# qtip_rev2.net
KiCad netlist of a schematic drawn in EAGLE
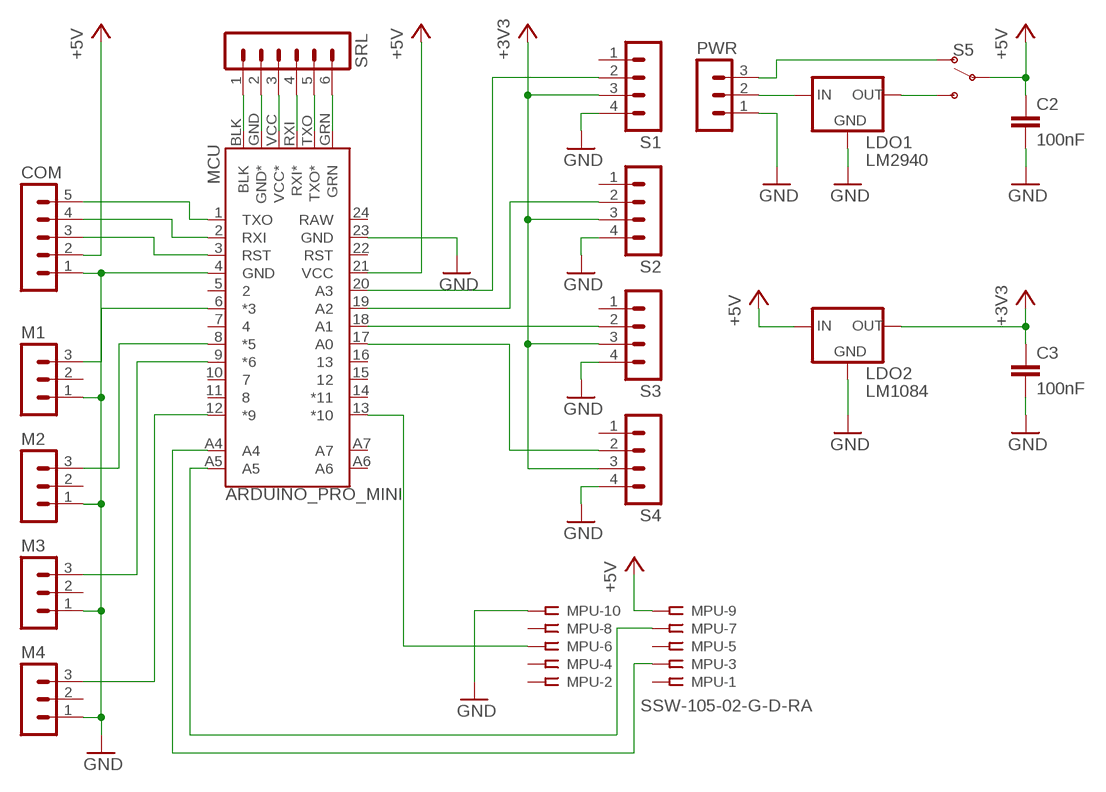
[diagram p0: schematic, sheet 1]

(export (version "E")
  (design (tool "Eeschema 10.0.6"))
  (components
    (comp (ref "C2")
      (value "100nF")
      (footprint "eagle-import:C025-024X044")
      (libsource (lib "eagle-import") (part "C-EU025-024X044"))
    )
    (comp (ref "C3")
      (value "100nF")
      (footprint "eagle-import:C025-024X044")
      (libsource (lib "eagle-import") (part "C-EU025-024X044"))
    )
    (comp (ref "COM")
      (value "MA05-1")
      (footprint "eagle-import:MA05-1")
      (fields (field (name "SPICEPREFIX") "X"))
      (libsource (lib "eagle-import") (part "MA05-1"))
    )
    (comp (ref "LDO1")
      (value "LM2940")
      (footprint "eagle-import:78XXL")
      (libsource (lib "eagle-import") (part "V_REG_LD1117VXX"))
    )
    (comp (ref "LDO2")
      (value "LM1084")
      (footprint "eagle-import:78XXL")
      (libsource (lib "eagle-import") (part "V_REG_LD1117VXX"))
    )
    (comp (ref "M1")
      (value "MA03-1")
      (footprint "eagle-import:MA03-1")
      (libsource (lib "eagle-import") (part "MA03-1"))
    )
    (comp (ref "M2")
      (value "MA03-1")
      (footprint "eagle-import:MA03-1")
      (libsource (lib "eagle-import") (part "MA03-1"))
    )
    (comp (ref "M3")
      (value "MA03-1")
      (footprint "eagle-import:MA03-1")
      (libsource (lib "eagle-import") (part "MA03-1"))
    )
    (comp (ref "M4")
      (value "MA03-1")
      (footprint "eagle-import:MA03-1")
      (libsource (lib "eagle-import") (part "MA03-1"))
    )
    (comp (ref "MCU")
      (value "ARDUINO_PRO_MINI")
      (footprint "eagle-import:ARDUINO_PRO_MINI")
      (libsource (lib "eagle-import") (part "ARDUINO_PRO_MINI"))
    )
    (comp (ref "MPU")
      (value "SSW-105-02-G-D-RA")
      (footprint "eagle-import:SSW-105-02-G-D-RA")
      (fields (field (name "MF") "Samtec Inc."))
      (libsource (lib "eagle-import") (part "SSW-105-02-G-D-RA"))
    )
    (comp (ref "PWR")
      (value "MA03-1")
      (footprint "eagle-import:MA03-1")
      (libsource (lib "eagle-import") (part "MA03-1"))
    )
    (comp (ref "S1")
      (value "MA04-1")
      (footprint "eagle-import:MA04-1")
      (libsource (lib "eagle-import") (part "MA04-1"))
    )
    (comp (ref "S2")
      (value "MA04-1")
      (footprint "eagle-import:MA04-1")
      (libsource (lib "eagle-import") (part "MA04-1"))
    )
    (comp (ref "S3")
      (value "MA04-1")
      (footprint "eagle-import:MA04-1")
      (libsource (lib "eagle-import") (part "MA04-1"))
    )
    (comp (ref "S4")
      (value "MA04-1")
      (footprint "eagle-import:MA04-1")
      (libsource (lib "eagle-import") (part "MA04-1"))
    )
    (comp (ref "S5")
      (value "SWITCH-SPDT-PTH-11.6X4.0MM")
      (footprint "eagle-import:SWITCH_SPDT_PTH_11.6X4.0MM")
      (libsource (lib "eagle-import") (part "SWITCH-SPDT-PTH-11.6X4.0MM"))
    )
    (comp (ref "SRL")
      (value "MA06-1")
      (footprint "eagle-import:MA06-1")
      (libsource (lib "eagle-import") (part "MA06-1"))
    )
  )
  (nets
    (net (code "1") (name "+3V3") (class "Default")
      (node (ref "C3") (pin "1") (pinfunction "1_1") (pintype "passive"))
      (node (ref "LDO2") (pin "GND") (pinfunction "OUT_GND") (pintype "passive"))
      (node (ref "S1") (pin "3") (pinfunction "3_3") (pintype "passive"))
      (node (ref "S2") (pin "3") (pinfunction "3_3") (pintype "passive"))
      (node (ref "S3") (pin "3") (pinfunction "3_3") (pintype "passive"))
      (node (ref "S4") (pin "3") (pinfunction "3_3") (pintype "passive"))
    )
    (net (code "2") (name "+5V") (class "Default")
      (node (ref "C2") (pin "1") (pinfunction "1_1") (pintype "passive"))
      (node (ref "COM") (pin "2") (pinfunction "2_2") (pintype "passive"))
      (node (ref "LDO2") (pin "OUT") (pinfunction "IN_OUT") (pintype "input"))
      (node (ref "MCU") (pin "21") (pinfunction "VCC_21") (pintype "power_in"))
      (node (ref "MPU") (pin "9") (pinfunction "1_9") (pintype "passive"))
      (node (ref "S5") (pin "2") (pinfunction "P_2") (pintype "passive"))
    )
    (net (code "3") (name "/RAW") (class "Default")
      (node (ref "MCU") (pin "24") (pinfunction "RAW_24") (pintype "power_in"))
    )
    (net (code "4") (name "GND") (class "Default")
      (node (ref "C2") (pin "2") (pinfunction "2_2") (pintype "passive"))
      (node (ref "C3") (pin "2") (pinfunction "2_2") (pintype "passive"))
      (node (ref "COM") (pin "1") (pinfunction "1_1") (pintype "passive"))
      (node (ref "LDO1") (pin "IN") (pinfunction "GND_IN") (pintype "input"))
      (node (ref "LDO2") (pin "IN") (pinfunction "GND_IN") (pintype "input"))
      (node (ref "M1") (pin "1") (pinfunction "1_1") (pintype "passive"))
      (node (ref "M2") (pin "1") (pinfunction "1_1") (pintype "passive"))
      (node (ref "M3") (pin "1") (pinfunction "1_1") (pintype "passive"))
      (node (ref "M4") (pin "1") (pinfunction "1_1") (pintype "passive"))
      (node (ref "MCU") (pin "23") (pinfunction "GND_23") (pintype "power_in"))
      (node (ref "MCU") (pin "4") (pinfunction "GND_4") (pintype "power_in"))
      (node (ref "MPU") (pin "10") (pinfunction "1_10") (pintype "passive"))
      (node (ref "PWR") (pin "1") (pinfunction "1_1") (pintype "passive"))
      (node (ref "S1") (pin "4") (pinfunction "4_4") (pintype "passive"))
      (node (ref "S2") (pin "4") (pinfunction "4_4") (pintype "passive"))
      (node (ref "S3") (pin "4") (pinfunction "4_4") (pintype "passive"))
      (node (ref "S4") (pin "4") (pinfunction "4_4") (pintype "passive"))
    )
    (net (code "5") (name "Net-(COM-Pad3)") (class "Default")
      (node (ref "COM") (pin "3") (pinfunction "3_3") (pintype "passive"))
      (node (ref "MCU") (pin "3") (pinfunction "RST_3") (pintype "bidirectional"))
    )
    (net (code "6") (name "Net-(LDO1-IN)") (class "Default")
      (node (ref "LDO1") (pin "OUT") (pinfunction "IN_OUT") (pintype "input"))
      (node (ref "PWR") (pin "2") (pinfunction "2_2") (pintype "passive"))
    )
    (net (code "7") (name "Net-(LDO1-OUT)") (class "Default")
      (node (ref "LDO1") (pin "GND") (pinfunction "OUT_GND") (pintype "passive"))
      (node (ref "S5") (pin "3") (pinfunction "S_3") (pintype "passive"))
    )
    (net (code "8") (name "Net-(MCU-*3)") (class "Default")
      (node (ref "M1") (pin "3") (pinfunction "3_3") (pintype "passive"))
      (node (ref "MCU") (pin "6") (pinfunction "*3_6") (pintype "bidirectional"))
    )
    (net (code "9") (name "Net-(MCU-*5)") (class "Default")
      (node (ref "M2") (pin "3") (pinfunction "3_3") (pintype "passive"))
      (node (ref "MCU") (pin "8") (pinfunction "*5_8") (pintype "bidirectional"))
    )
    (net (code "10") (name "Net-(MCU-*6)") (class "Default")
      (node (ref "M3") (pin "3") (pinfunction "3_3") (pintype "passive"))
      (node (ref "MCU") (pin "9") (pinfunction "*6_9") (pintype "bidirectional"))
    )
    (net (code "11") (name "Net-(MCU-*9)") (class "Default")
      (node (ref "M4") (pin "3") (pinfunction "3_3") (pintype "passive"))
      (node (ref "MCU") (pin "12") (pinfunction "*9_12") (pintype "bidirectional"))
    )
    (net (code "12") (name "Net-(MCU-*10)") (class "Default")
      (node (ref "MCU") (pin "13") (pinfunction "*10_13") (pintype "bidirectional"))
      (node (ref "MPU") (pin "6") (pinfunction "1_6") (pintype "passive"))
    )
    (net (code "13") (name "Net-(MCU-A0)") (class "Default")
      (node (ref "MCU") (pin "17") (pinfunction "A0_17") (pintype "bidirectional"))
      (node (ref "S4") (pin "2") (pinfunction "2_2") (pintype "passive"))
    )
    (net (code "14") (name "Net-(MCU-A1)") (class "Default")
      (node (ref "MCU") (pin "18") (pinfunction "A1_18") (pintype "bidirectional"))
      (node (ref "S3") (pin "2") (pinfunction "2_2") (pintype "passive"))
    )
    (net (code "15") (name "Net-(MCU-A2)") (class "Default")
      (node (ref "MCU") (pin "19") (pinfunction "A2_19") (pintype "bidirectional"))
      (node (ref "S2") (pin "2") (pinfunction "2_2") (pintype "passive"))
    )
    (net (code "16") (name "Net-(MCU-A3)") (class "Default")
      (node (ref "MCU") (pin "20") (pinfunction "A3_20") (pintype "bidirectional"))
      (node (ref "S1") (pin "2") (pinfunction "2_2") (pintype "passive"))
    )
    (net (code "17") (name "Net-(MCU-GND*)") (class "Default")
      (node (ref "MCU") (pin "GND") (pinfunction "GND*_GND") (pintype "bidirectional"))
      (node (ref "SRL") (pin "2") (pinfunction "2_2") (pintype "passive"))
    )
    (net (code "18") (name "Net-(MCU-PadBLK)") (class "Default")
      (node (ref "MCU") (pin "BLK") (pinfunction "BLK_BLK") (pintype "bidirectional"))
      (node (ref "SRL") (pin "1") (pinfunction "1_1") (pintype "passive"))
    )
    (net (code "19") (name "Net-(MCU-PadGRN)") (class "Default")
      (node (ref "MCU") (pin "GRN") (pinfunction "GRN_GRN") (pintype "bidirectional"))
      (node (ref "SRL") (pin "6") (pinfunction "6_6") (pintype "passive"))
    )
    (net (code "20") (name "Net-(MCU-RXI)") (class "Default")
      (node (ref "COM") (pin "4") (pinfunction "4_4") (pintype "passive"))
      (node (ref "MCU") (pin "2") (pinfunction "RXI_2") (pintype "bidirectional"))
    )
    (net (code "21") (name "Net-(MCU-RXI*)") (class "Default")
      (node (ref "MCU") (pin "RXI") (pinfunction "RXI*_RXI") (pintype "bidirectional"))
      (node (ref "SRL") (pin "4") (pinfunction "4_4") (pintype "passive"))
    )
    (net (code "22") (name "Net-(MCU-TXO)") (class "Default")
      (node (ref "COM") (pin "5") (pinfunction "5_5") (pintype "passive"))
      (node (ref "MCU") (pin "1") (pinfunction "TXO_1") (pintype "bidirectional"))
    )
    (net (code "23") (name "Net-(MCU-TXO*)") (class "Default")
      (node (ref "MCU") (pin "TXO") (pinfunction "TXO*_TXO") (pintype "bidirectional"))
      (node (ref "SRL") (pin "5") (pinfunction "5_5") (pintype "passive"))
    )
    (net (code "24") (name "Net-(MCU-VCC*)") (class "Default")
      (node (ref "MCU") (pin "VCC") (pinfunction "VCC*_VCC") (pintype "bidirectional"))
      (node (ref "SRL") (pin "3") (pinfunction "3_3") (pintype "passive"))
    )
    (net (code "25") (name "Net-(MPUD-1)") (class "Default")
      (node (ref "MCU") (pin "A4") (pinfunction "A4_A4") (pintype "bidirectional"))
      (node (ref "MPU") (pin "3") (pinfunction "1_3") (pintype "passive"))
    )
    (net (code "26") (name "Net-(MPUH-1)") (class "Default")
      (node (ref "MCU") (pin "A5") (pinfunction "A5_A5") (pintype "bidirectional"))
      (node (ref "MPU") (pin "7") (pinfunction "1_7") (pintype "passive"))
    )
    (net (code "27") (name "Net-(S5-O)") (class "Default")
      (node (ref "PWR") (pin "3") (pinfunction "3_3") (pintype "passive"))
      (node (ref "S5") (pin "1") (pinfunction "O_1") (pintype "passive"))
    )
    (net (code "28") (name "unconnected-(M1-Pad2)") (class "Default")
      (node (ref "M1") (pin "2") (pinfunction "2_2") (pintype "passive"))
    )
    (net (code "29") (name "unconnected-(M2-Pad2)") (class "Default")
      (node (ref "M2") (pin "2") (pinfunction "2_2") (pintype "passive"))
    )
    (net (code "30") (name "unconnected-(M3-Pad2)") (class "Default")
      (node (ref "M3") (pin "2") (pinfunction "2_2") (pintype "passive"))
    )
    (net (code "31") (name "unconnected-(M4-Pad2)") (class "Default")
      (node (ref "M4") (pin "2") (pinfunction "2_2") (pintype "passive"))
    )
    (net (code "32") (name "unconnected-(MCU-*11-Pad14)") (class "Default")
      (node (ref "MCU") (pin "14") (pinfunction "*11_14") (pintype "bidirectional"))
    )
    (net (code "33") (name "unconnected-(MCU-2-Pad5)") (class "Default")
      (node (ref "MCU") (pin "5") (pinfunction "2_5") (pintype "bidirectional"))
    )
    (net (code "34") (name "unconnected-(MCU-4-Pad7)") (class "Default")
      (node (ref "MCU") (pin "7") (pinfunction "4_7") (pintype "bidirectional"))
    )
    (net (code "35") (name "unconnected-(MCU-7-Pad10)") (class "Default")
      (node (ref "MCU") (pin "10") (pinfunction "7_10") (pintype "bidirectional"))
    )
    (net (code "36") (name "unconnected-(MCU-8-Pad11)") (class "Default")
      (node (ref "MCU") (pin "11") (pinfunction "8_11") (pintype "bidirectional"))
    )
    (net (code "37") (name "unconnected-(MCU-12-Pad15)") (class "Default")
      (node (ref "MCU") (pin "15") (pinfunction "12_15") (pintype "bidirectional"))
    )
    (net (code "38") (name "unconnected-(MCU-13-Pad16)") (class "Default")
      (node (ref "MCU") (pin "16") (pinfunction "13_16") (pintype "bidirectional"))
    )
    (net (code "39") (name "unconnected-(MCU-PadA6)") (class "Default")
      (node (ref "MCU") (pin "A6") (pinfunction "A6_A6") (pintype "bidirectional"))
    )
    (net (code "40") (name "unconnected-(MCU-PadA7)") (class "Default")
      (node (ref "MCU") (pin "A7") (pinfunction "A7_A7") (pintype "bidirectional"))
    )
    (net (code "41") (name "unconnected-(MCU-RST-Pad22)") (class "Default")
      (node (ref "MCU") (pin "22") (pinfunction "RST_22") (pintype "bidirectional"))
    )
    (net (code "42") (name "unconnected-(MPU-Pad1)") (class "Default")
      (node (ref "MPU") (pin "1") (pinfunction "1_1") (pintype "passive"))
    )
    (net (code "43") (name "unconnected-(MPUC-1-Pad2)") (class "Default")
      (node (ref "MPU") (pin "2") (pinfunction "1_2") (pintype "passive"))
    )
    (net (code "44") (name "unconnected-(MPUE-1-Pad4)") (class "Default")
      (node (ref "MPU") (pin "4") (pinfunction "1_4") (pintype "passive"))
    )
    (net (code "45") (name "unconnected-(MPUF-1-Pad5)") (class "Default")
      (node (ref "MPU") (pin "5") (pinfunction "1_5") (pintype "passive"))
    )
    (net (code "46") (name "unconnected-(MPUI-1-Pad8)") (class "Default")
      (node (ref "MPU") (pin "8") (pinfunction "1_8") (pintype "passive"))
    )
    (net (code "47") (name "unconnected-(S1-Pad1)") (class "Default")
      (node (ref "S1") (pin "1") (pinfunction "1_1") (pintype "passive"))
    )
    (net (code "48") (name "unconnected-(S2-Pad1)") (class "Default")
      (node (ref "S2") (pin "1") (pinfunction "1_1") (pintype "passive"))
    )
    (net (code "49") (name "unconnected-(S3-Pad1)") (class "Default")
      (node (ref "S3") (pin "1") (pinfunction "1_1") (pintype "passive"))
    )
    (net (code "50") (name "unconnected-(S4-Pad1)") (class "Default")
      (node (ref "S4") (pin "1") (pinfunction "1_1") (pintype "passive"))
    )
  )
)
